# MAINSSMB_V1_4.net
KiCad netlist of a schematic drawn in Altium Designer
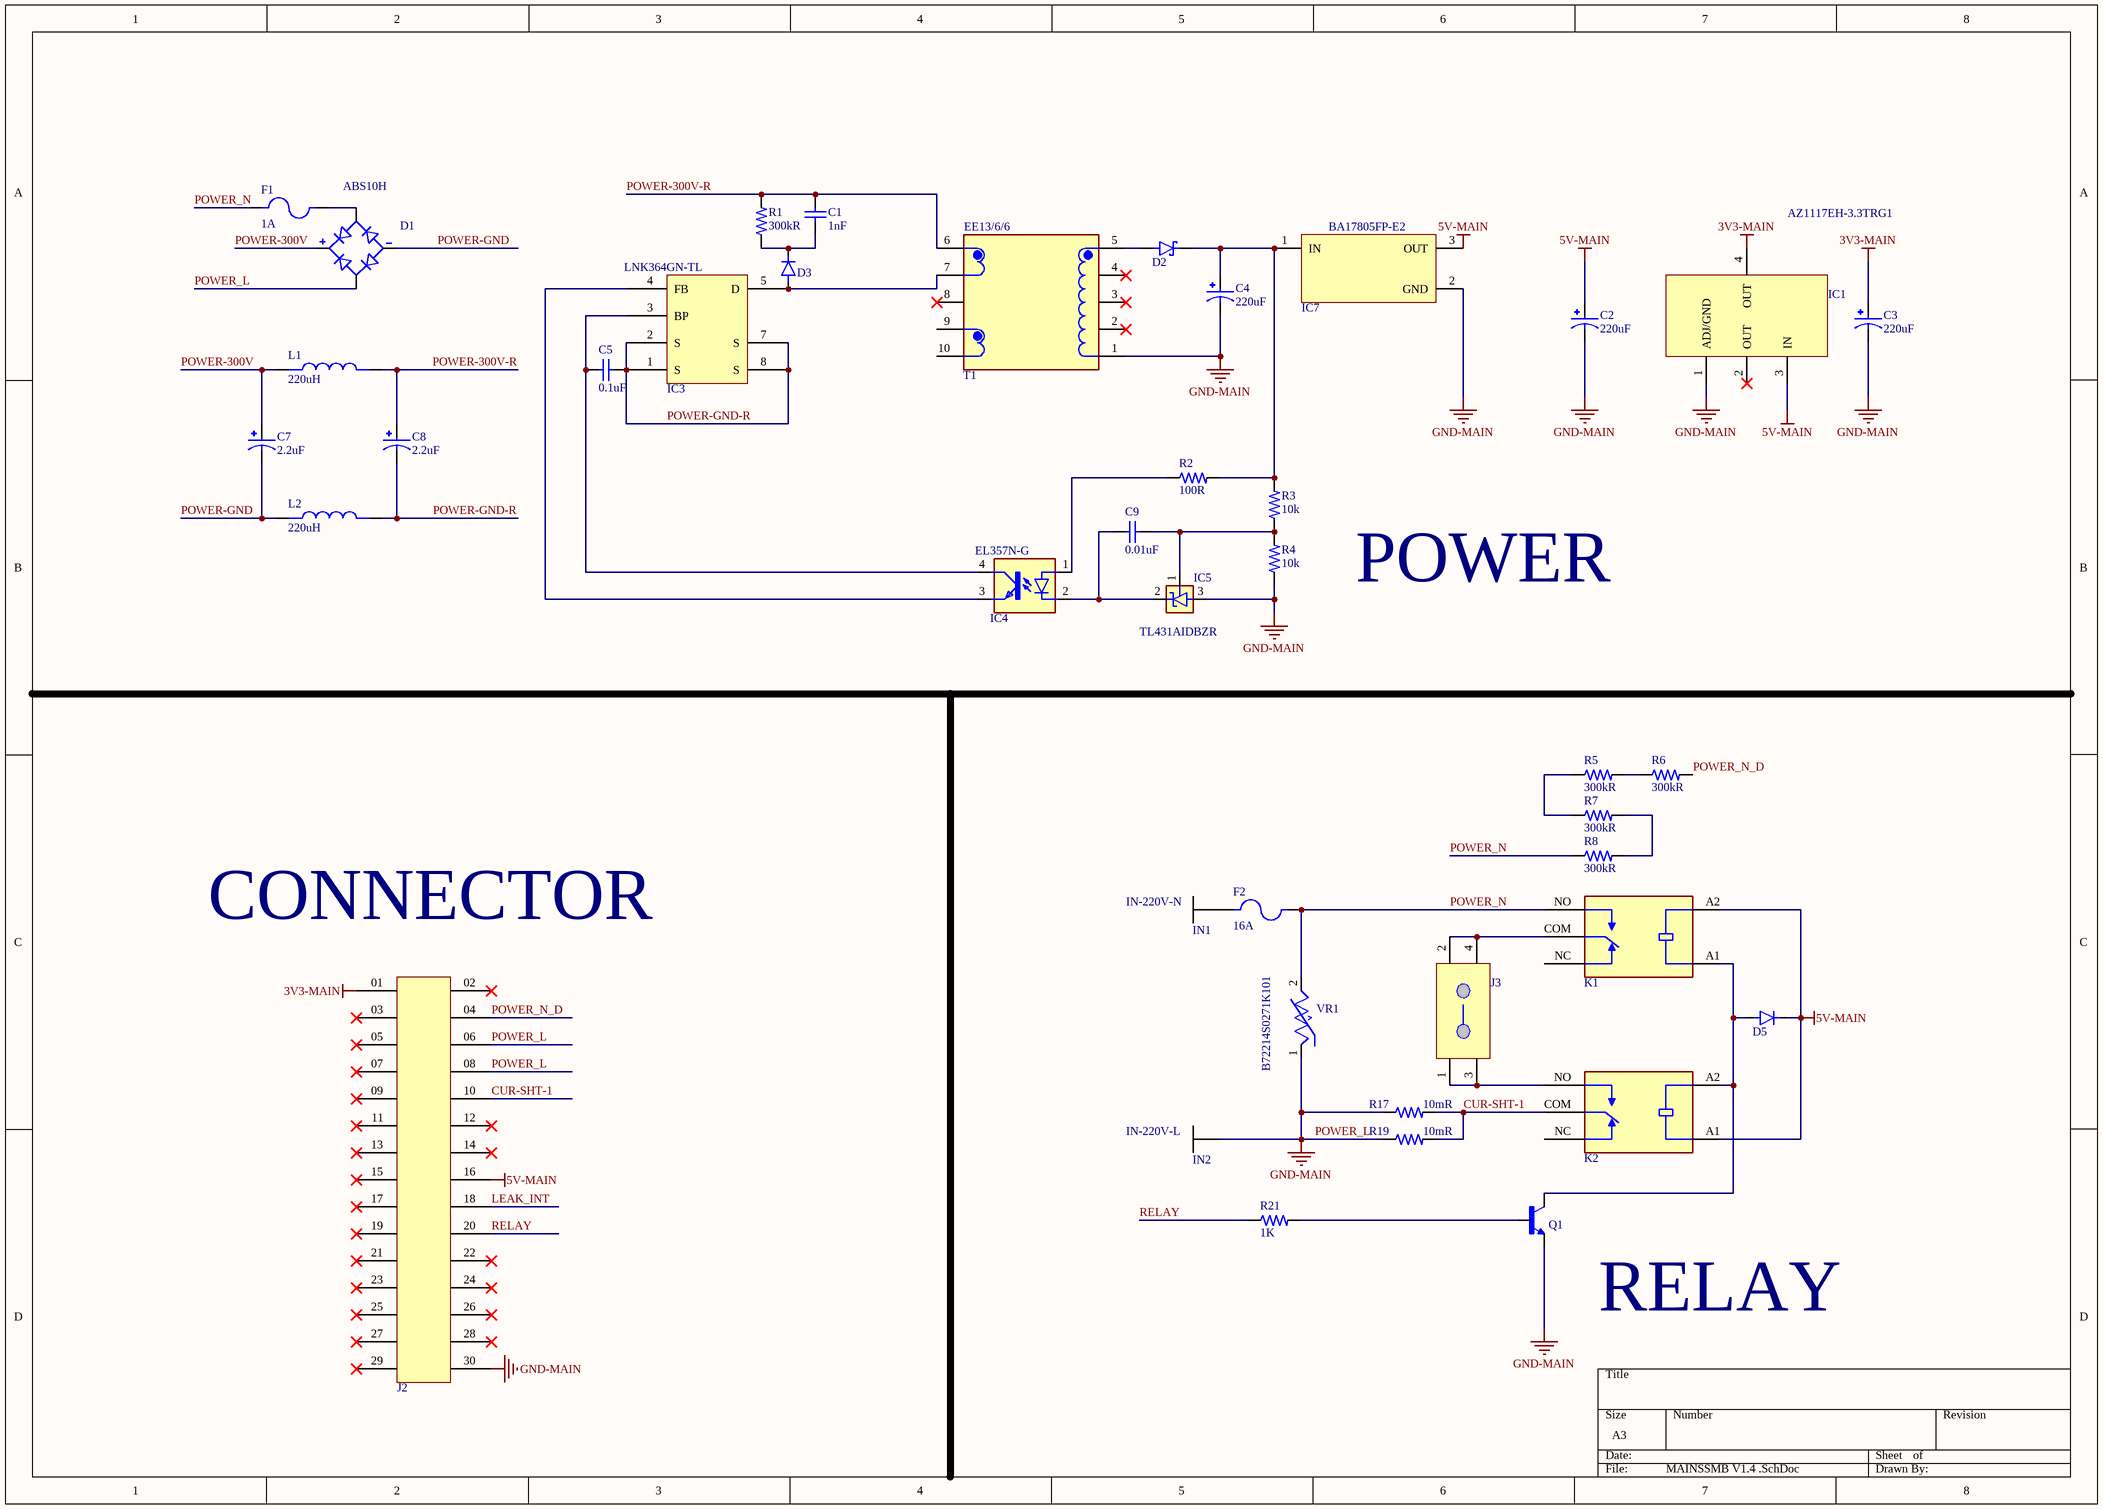
[diagram p0: MAINSSMB V1.4 .SchDoc]

(export (version "E")
  (design (tool "Eeschema 10.0.6"))
  (components
    (comp (ref "C1")
      (value "1nF")
      (footprint "TH-CAP-HxLxW-5.5x4.0x2.5-TDKC")
      (description "Capacitor Ceramic 0.001uF 50V C0G 5% 5mm T/R")
      (fields
        (field (name "MANUFACTURER") "TDK")
        (field (name "MANUFACTURER PART NUMBER") "FA28NP01H102JNU06")
        (field (name "DESIGNER") "TVBac")
      )
      (libsource (lib "Capacitors") (part "CAP; TH; 0.001uF; 50V; FA28NP01H102JNU06"))
    )
    (comp (ref "C2")
      (value "220uF")
      (footprint "SMD-DxLxW-6.3x6.6x6.6-PEC")
      (description "Cap Aluminum Polymer 220uF 16VDC 20% (6.3 X 5.9mm) SMD 0.022 Ohm 1040mA 1000h 125C T/R")
      (fields
        (field (name "MANUFACTURER") "Panasonic")
        (field (name "MANUFACTURER PART NUMBER") "16SVPK220M")
        (field (name "DESIGNER") "TVBac")
      )
      (libsource (lib "Capacitors") (part "CAP; 220uF; 16V; SMD; 16SVPK220M"))
    )
    (comp (ref "C3")
      (value "220uF")
      (footprint "SMD-DxLxW-6.3x6.6x6.6-PEC")
      (description "Cap Aluminum Polymer 220uF 10VDC 20%( 6.3 X 5.9mm) SMD 0.02 Ohm 2700mA 2000h 105C T/R")
      (fields
        (field (name "MANUFACTURER") "Panasonic")
        (field (name "MANUFACTURER PART NUMBER") "10SVPE220M")
        (field (name "DESIGNER") "TVBac")
      )
      (libsource (lib "Capacitors") (part "CAP; 220uF; 10V; SMD; 10SVPE220M"))
    )
    (comp (ref "C4")
      (value "220uF")
      (footprint "SMD-DxLxW-6.3x6.6x6.6-PEC")
      (description "Cap Aluminum Polymer 220uF 16VDC 20% (6.3 X 5.9mm) SMD 0.022 Ohm 1040mA 1000h 125C T/R")
      (fields
        (field (name "MANUFACTURER") "Panasonic")
        (field (name "MANUFACTURER PART NUMBER") "16SVPK220M")
        (field (name "DESIGNER") "TVBac")
      )
      (libsource (lib "Capacitors") (part "CAP; 220uF; 16V; SMD; 16SVPK220M"))
    )
    (comp (ref "C5")
      (value "0.1uF")
      (footprint "SMD-CAP-0603-YAGEO")
      (description "Multilayer Ceramic Capacitor, 0.1 uF, 50 V, ï¿½ 5%, X7R, 0603 [1608 Metric]")
      (fields
        (field (name "MANUFACTURER") "Yageo")
        (field (name "MANUFACTURER PART NUMBER") "CC0603JRX7R9BB104")
        (field (name "DESIGNER") "TVBac")
      )
      (libsource (lib "Capacitors") (part "CAP; 0.1uF; 50V; 0603; SMD; CC0603JRX7R9BB104"))
    )
    (comp (ref "C7")
      (value "2.2uF")
      (footprint "TH-CAP-HxD-12.5x8.0-PEC")
      (description "Cap Aluminum Lytic 2.2uF 400V 20% (8 X 11.5mm) Radial 3.5mm 50mA 2000h 85C Automotive Bulk")
      (fields
        (field (name "MANUFACTURER") "Panasonic")
        (field (name "MANUFACTURER PART NUMBER") "ECA-2GM2R2")
        (field (name "DESIGNER") "TVBac")
      )
      (libsource (lib "Capacitors") (part "CAP; TH; 2.2uF; 400V; ECA-2GM2R2"))
    )
    (comp (ref "C8")
      (value "2.2uF")
      (footprint "TH-CAP-HxD-12.5x8.0-PEC")
      (description "Cap Aluminum Lytic 2.2uF 400V 20% (8 X 11.5mm) Radial 3.5mm 50mA 2000h 85C Automotive Bulk")
      (fields
        (field (name "MANUFACTURER") "Panasonic")
        (field (name "MANUFACTURER PART NUMBER") "ECA-2GM2R2")
        (field (name "DESIGNER") "TVBac")
      )
      (libsource (lib "Capacitors") (part "CAP; TH; 2.2uF; 400V; ECA-2GM2R2"))
    )
    (comp (ref "C9")
      (value "0.01uF")
      (footprint "SMD-CAP-0603-YAGEO")
      (description "Surface Mount Ceramic Multilayer Capacitor 0.01uF 5% X7R 25V 0603 Paper T/R")
      (fields
        (field (name "MANUFACTURER") "Yageo")
        (field (name "MANUFACTURER PART NUMBER") "CC0603JRX7R8BB103")
        (field (name "DESIGNER") "TVBac")
      )
      (libsource (lib "Capacitors") (part "CAP; 0.01uF; 25V; 0603; SMD; CC0603JRX7R8BB103"))
    )
    (comp (ref "D1")
      (value "Bridge Rectifier Single Phase Standard 1 kV Surface Mount ABS")
      (footprint "DIODE-SMD-4-TSC")
      (description "Bridge Rectifiers 1A, 1000V, Standard Bridge Rectifier")
      (fields
        (field (name "MANUFACTURER") "Taiwan Semiconductor")
        (field (name "MANUFACTURER PART NUMBER") "ABS10H")
        (field (name "DESIGNER") "TVBac")
      )
      (libsource (lib "Diode") (part "DIODE; SMD; ABS10H"))
    )
    (comp (ref "D2")
      (value "Diode 40 V 3A Surface Mount DO-214AC (SMA)")
      (footprint "SMD-DO-214AC-214-CT")
      (description "Diode Schottky Si 40V 3A 2-Pin SMA T/R")
      (fields
        (field (name "MANUFACTURER") "Comchip")
        (field (name "MANUFACTURER PART NUMBER") "SS34-HF")
        (field (name "DESIGNER") "TVBac")
      )
      (libsource (lib "Smartsocket") (part "DIODE; SMD; SCHOTTKY; SS34-HF"))
    )
    (comp (ref "D3")
      (value "Diode 1000 V 1A Surface Mount SOD-123FL")
      (footprint "SOD-123FL-SMCDS")
      (description "Diode Gen Purp 1KV 1A SOD123FL")
      (fields
        (field (name "MANUFACTURER") "Sangdest Microelectronics")
        (field (name "MANUFACTURER PART NUMBER") "1N4007FL")
        (field (name "DESIGNER") "TVBac")
      )
      (libsource (lib "Diode") (part "DIODE; SMD; 1N4007FLN4007;"))
    )
    (comp (ref "D5")
      (value "Diode 1000 V 1A Surface Mount SOD-123FL")
      (footprint "SOD-123FL-SMCDS")
      (description "Diode Gen Purp 1KV 1A SOD123FL")
      (fields
        (field (name "MANUFACTURER") "Sangdest Microelectronics")
        (field (name "MANUFACTURER PART NUMBER") "1N4007FL")
        (field (name "DESIGNER") "TVBac")
      )
      (libsource (lib "Diode") (part "DIODE; SMD; 1N4007FLN4007;"))
    )
    (comp (ref "F1")
      (value "1A")
      (footprint "FUSE-HxLxW-8.0x8.5x4.0-LI")
      (description "Fuse Subminiature Slow Blow Acting 1A 300V Radial 8.5 X 4 X 8mm Ammo Pack")
      (fields
        (field (name "MANUFACTURER") "Littelfuse Wickmann")
        (field (name "MANUFACTURER PART NUMBER") "36911000000")
        (field (name "DESIGNER") "TVBac")
      )
      (libsource (lib "Smartsocket") (part "FUSE; 1A; 36911000000"))
    )
    (comp (ref "F2")
      (value "16A")
      (footprint "FUSE-3.6mmx10mm-AXIAL")
      (fields
        (field (name "MANUFACTURER") "Schurter")
        (field (name "MANUFACTURER PART NUMBER") "0031.8211")
        (field (name "Comment") "FUSE; 16A; 0031.8211_1")
        (field (name "DESIGNER") "TVBac")
      )
      (libsource (lib "Socket") (part "FUSE; 16A; 0031.8211_1"))
    )
    (comp (ref "IC1")
      (value "Linear Voltage Regulator IC Positive Fixed 1 Output 1A SOT-223-3")
      (footprint "IC:SOT-223-3-DI")
      (description "Linear Voltage Regulator IC 1 Output 1A SOT-223")
      (fields
        (field (name "MF") "Diodes Inc.")
        (field (name "MP") "AZ1117EH-3.3TRG1")
        (field (name "DESIGNER") "TVBac")
      )
      (libsource (lib "IC") (part "LDO; 3V3; 1A; SMD; AZ1117EH-3.3TRG1"))
    )
    (comp (ref "IC3")
      (value "Converter Offline Flyback Topology 132kHz SMD-8B")
      (footprint "SMD-8B-PI")
      (description "AC to DC Switching Converter Off-Line Switcher 140kHz 7-Pin SMD-B / IC OFFLINE SWIT HV 8SMD")
      (fields
        (field (name "MANUFACTURER") "Power Integrations")
        (field (name "MANUFACTURER PART NUMBER") "LNK364GN-TL")
        (field (name "DESIGNER") "TVBac")
      )
      (libsource (lib "Smartsocket") (part "LNK364GN-TL"))
    )
    (comp (ref "IC4")
      (value "Optoisolator Transistor Output 3750Vrms 1 Channel 4-SOP (2.54mm)")
      (footprint "SOP-4")
      (description "Transistor Output Optocoupler, 1-Element, 3750V Isolation")
      (fields (field (name "MANUFACTURER") "Everlight") (field (name "MANUFACTURER PART NUMBER") "EL357N-G"))
      (libsource (lib "IC") (part "ISO; 1CH; EL357N-G"))
    )
    (comp (ref "IC5")
      (value "Shunt Voltage Reference IC Adjustable 2.495V 36 VV ±1% 100 mA SOT-23-3")
      (footprint "SOT-23-3-DS")
      (description "V-Ref Adjustable 2.495V to 36V 100mA Automotive 3-Pin SOT-23 T/R")
      (fields
        (field (name "MANUFACTURER") "Texas Instruments")
        (field (name "MANUFACTURER PART NUMBER") "TL431AIDBZR")
        (field (name "TOLERANCE") "1%")
        (field (name "DESIGNER") "TVBac")
      )
      (libsource (lib "IC") (part "TL431AIDBZR; MIRROID;"))
    )
    (comp (ref "IC7")
      (value "Linear Voltage Regulator IC Positive Fixed 1 Output 1A TO-252")
      (footprint "TO252-3-RS")
      (description "Linear Voltage Regulator, Fixed, Positive Output, 7.5 V to 25 V, 5V, 1A, 3 Pins, TO-252 (DPAK)")
      (fields
        (field (name "MANUFACTURER") "Rohm")
        (field (name "MANUFACTURER PART NUMBER") "BA17805FP-E2")
        (field (name "DESIGNER") "TVBac")
      )
      (libsource (lib "IC") (part "LDO; 5V; 1A; BA17805FP-E2"))
    )
    (comp (ref "IN1")
      (value "INPUT")
      (footprint "INPUT-2.0x3.5")
      (fields (field (name "DESIGNER") "TVBac"))
      (libsource (lib "Socket") (part "INPUT-2.0x3.5"))
    )
    (comp (ref "IN2")
      (value "INPUT")
      (footprint "INPUT-2.0x3.5")
      (fields (field (name "DESIGNER") "TVBac"))
      (libsource (lib "Socket") (part "INPUT-2.0x3.5"))
    )
    (comp (ref "J2")
      (value "30 Position Elevated Socket Connector 0.100\" (2.54mm) Through Hole Gold")
      (footprint "HEADER-2.54-15x2-N3D")
      (description "Connector Receptacle 30 Position 0.100\" (2.54mm) Gold Through Hole")
      (fields
        (field (name "MANUFACTURER") "Samtec")
        (field (name "MANUFACTURER PART NUMBER") "ESQ-115-12-G-D")
        (field (name "DESIGNER") "TVBac")
      )
      (libsource (lib "Socket") (part "HEADER; 15x2PIN; 2.54; VER; ESQ-115-12-G-D; N3D"))
    )
    (comp (ref "J3")
      (value "Connector Header Through Hole 4 position 0.100\" (2.54mm)")
      (footprint "SOCKET-SINGLE-WEV1081H")
      (description "Conn Unshrouded Header HDR 4 POS 2.54mm Solder ST Thru-Hole Automotive Bulk")
      (fields
        (field (name "MANUFACTURER") "Samtec")
        (field (name "MANUFACTURER PART NUMBER") "TSW-104-14-L-S")
        (field (name "DESIGNER") "TVBac")
      )
      (libsource (lib "Socket") (part "SOCKET; SINGLE;"))
    )
    (comp (ref "K1")
      (value "JQ1P-5V-F")
      (footprint "RELAY-JQ1P-10A-HxLxW-15.6x20.5x10.0-PEW")
      (description "RELAY GEN PURPOSE SPDT 10A 5V")
      (fields (field (name "DESIGNER") "TVBac"))
      (libsource (lib "Relay") (part "RELAY; SINGLE; 5VDC; CMP-05607-000163-1"))
    )
    (comp (ref "K2")
      (value "JQ1P-5V-F")
      (footprint "RELAY-JQ1P-10A-HxLxW-15.6x20.5x10.0-PEW")
      (description "RELAY GEN PURPOSE SPDT 10A 5V")
      (fields (field (name "DESIGNER") "TVBac"))
      (libsource (lib "Relay") (part "RELAY; SINGLE; 5VDC; CMP-05607-000163-1"))
    )
    (comp (ref "L1")
      (value "220uH")
      (footprint "SMD-HxLxW-1.8x4.0x4.0-ALLC")
      (description "Power Inductor (SMD), 220 uH, ± 20%, 250 mA, Shielded, 330 mA, 4mm x 4mm x 1.8mm")
      (fields
        (field (name "MANUFACTURER") "Abracon")
        (field (name "MANUFACTURER PART NUMBER") "ASPI-0418FS-221M-T3")
        (field (name "DESIGNER") "TVBac")
      )
      (libsource (lib "Inductors") (part "IND; 220uH; 250mA; ASPI-0418FS-221M-T3"))
    )
    (comp (ref "L2")
      (value "220uH")
      (footprint "SMD-HxLxW-1.8x4.0x4.0-ALLC")
      (description "Power Inductor (SMD), 220 uH, ± 20%, 250 mA, Shielded, 330 mA, 4mm x 4mm x 1.8mm")
      (fields
        (field (name "MANUFACTURER") "Abracon")
        (field (name "MANUFACTURER PART NUMBER") "ASPI-0418FS-221M-T3")
        (field (name "DESIGNER") "TVBac")
      )
      (libsource (lib "Inductors") (part "IND; 220uH; 250mA; ASPI-0418FS-221M-T3"))
    )
    (comp (ref "Q1")
      (value "Bipolar (BJT) Transistor NPN 45 V 500 mA 100MHz 300 mW Surface Mount SOT-23-3 (TO-236)")
      (footprint "SOT-23-3-ONSEMI")
      (description "Single Bipolar Transistor, NPN, 45 V, 500 mA, 225 mW, SOT-23 (TO-236), 3 Pins, Surface Mount")
      (fields
        (field (name "MANUFACTURER") "ON Semiconductor")
        (field (name "MANUFACTURER PART NUMBER") "BC817-25LT1G")
        (field (name "DESIGNER") "TVBac")
      )
      (libsource (lib "Transistors") (part "TRAN; NPN; 500mA;V;  BC817-25LT1G"))
    )
    (comp (ref "R1")
      (value "300kR")
      (footprint "SMD-RES-1206-RS")
      (description "Res Thick Film 1206 300K Ohm 1% 0.5W(1/2W) ±100ppm/C Epoxy Resin Pad SMD Automotive T/R")
      (fields
        (field (name "MANUFACTURER") "Rohm")
        (field (name "MANUFACTURER PART NUMBER") "ESR18EZPF3003")
        (field (name "DESIGNER") "TVBac")
      )
      (libsource (lib "Resistors") (part "RES; 300K; 1206; ESR18EZPF3003"))
    )
    (comp (ref "R2")
      (value "100R")
      (footprint "SMD-RES-0603-RS")
      (description "Res Thick Film 0603 100 Ohm 1% 0.1W(1/10W) ±100ppm/C Pad SMD T/R Automotive AEC-Q200")
      (fields
        (field (name "MANUFACTURER") "Rohm")
        (field (name "MANUFACTURER PART NUMBER") "KTR03EZPF1000")
        (field (name "DESIGNER") "TVBac")
      )
      (libsource (lib "Resistors") (part "RES; 100R; 0603; SMD; KTR03EZPF1000"))
    )
    (comp (ref "R3")
      (value "10k")
      (footprint "SMD-RES-0603-SEI")
      (description "SMD Chip Resistor, 10 kOhm, ± 1%, 250 mW, 0603 [1608 Metric], Thick Film, Anti-Surge")
      (fields
        (field (name "MANUFACTURER") "Rohm")
        (field (name "MANUFACTURER PART NUMBER") "ESR03EZPF1002")
        (field (name "DESIGNER") "TVBac")
      )
      (libsource (lib "Resistors") (part "RES; 10K; 0603; SMD; ESR03EZPF1002"))
    )
    (comp (ref "R4")
      (value "10k")
      (footprint "SMD-RES-0603-SEI")
      (description "SMD Chip Resistor, 10 kOhm, ± 1%, 250 mW, 0603 [1608 Metric], Thick Film, Anti-Surge")
      (fields
        (field (name "MANUFACTURER") "Rohm")
        (field (name "MANUFACTURER PART NUMBER") "ESR03EZPF1002")
        (field (name "DESIGNER") "TVBac")
      )
      (libsource (lib "Resistors") (part "RES; 10K; 0603; SMD; ESR03EZPF1002"))
    )
    (comp (ref "R5")
      (value "300kR")
      (footprint "SMD-RES-0603-RS")
      (description "Res High Voltage Thick Film 0603 300k Ohm 1% 1/10W ±100ppm/°C Molded Paper T/R")
      (fields
        (field (name "MANUFACTURER") "Rohm")
        (field (name "MANUFACTURER PART NUMBER") "KTR03EZPF3003")
        (field (name "DESIGNER") "TVBac")
      )
      (libsource (lib "Resistors") (part "RES; 300K; 0603; SMD; KTR03EZPF3003"))
    )
    (comp (ref "R6")
      (value "300kR")
      (footprint "SMD-RES-0603-RS")
      (description "Res High Voltage Thick Film 0603 300k Ohm 1% 1/10W ±100ppm/°C Molded Paper T/R")
      (fields
        (field (name "MANUFACTURER") "Rohm")
        (field (name "MANUFACTURER PART NUMBER") "KTR03EZPF3003")
        (field (name "DESIGNER") "TVBac")
      )
      (libsource (lib "Resistors") (part "RES; 300K; 0603; SMD; KTR03EZPF3003"))
    )
    (comp (ref "R7")
      (value "300kR")
      (footprint "SMD-RES-0603-RS")
      (description "Res High Voltage Thick Film 0603 300k Ohm 1% 1/10W ±100ppm/°C Molded Paper T/R")
      (fields
        (field (name "MANUFACTURER") "Rohm")
        (field (name "MANUFACTURER PART NUMBER") "KTR03EZPF3003")
        (field (name "DESIGNER") "TVBac")
      )
      (libsource (lib "Resistors") (part "RES; 300K; 0603; SMD; KTR03EZPF3003"))
    )
    (comp (ref "R8")
      (value "300kR")
      (footprint "SMD-RES-0603-RS")
      (description "Res High Voltage Thick Film 0603 300k Ohm 1% 1/10W ±100ppm/°C Molded Paper T/R")
      (fields
        (field (name "MANUFACTURER") "Rohm")
        (field (name "MANUFACTURER PART NUMBER") "KTR03EZPF3003")
        (field (name "DESIGNER") "TVBac")
      )
      (libsource (lib "Resistors") (part "RES; 300K; 0603; SMD; KTR03EZPF3003"))
    )
    (comp (ref "R17")
      (value "10mR")
      (footprint "SMD-RES-2512-VD")
      (description "Res Current Sense Metal Plate 2512 0.01 Ohm 1% 3W ±110ppm/°C Molded T/R")
      (fields
        (field (name "MANUFACTURER") "Vishay")
        (field (name "MANUFACTURER PART NUMBER") "WFMA2512R0100FEA")
        (field (name "DESIGNER") "TVBac")
      )
      (libsource (lib "Smartsocket") (part "RES; SHUNT; 10mOhm; SMD; WFMA2512R0100FEA"))
    )
    (comp (ref "R19")
      (value "10mR")
      (footprint "SMD-RES-2512-VD")
      (description "Res Current Sense Metal Plate 2512 0.01 Ohm 1% 3W ±110ppm/°C Molded T/R")
      (fields
        (field (name "MANUFACTURER") "Vishay")
        (field (name "MANUFACTURER PART NUMBER") "WFMA2512R0100FEA")
        (field (name "DESIGNER") "TVBac")
      )
      (libsource (lib "Smartsocket") (part "RES; SHUNT; 10mOhm; SMD; WFMA2512R0100FEA"))
    )
    (comp (ref "R21")
      (value "1K")
      (footprint "SMD-RES-0603-SEI")
      (description "SMD Chip Resistor, 1 kOhm, ± 1%, 250 mW, 0603 [1608 Metric], Thick Film, Anti-Surge")
      (fields
        (field (name "MANUFACTURER") "Rohm")
        (field (name "MANUFACTURER PART NUMBER") "ESR03EZPF1001")
        (field (name "DESIGNER") "TVBac")
      )
      (libsource (lib "Smartsocket") (part "RES; 1K; 0603; SMD; ESR03EZPF1001"))
    )
    (comp (ref "T1")
      (value "For SMPS Transformer 500VAC Isolation Through Hole")
      (footprint "EE13 - POWER")
      (description "OFFLINE TRANSFORMER 6W EE13/7/6")
      (fields (field (name "MF") "Wurth Electronics Inc") (field (name "MP") "EE13/6/6"))
      (libsource (lib "Transformer") (part "EE13/6/6-Power"))
    )
    (comp (ref "VR1")
      (value "VAR; B72214S0271K101")
      (footprint "VARISTOR-TDK")
      (description "Var MOV 275VAC/350VDC 4500A 430V Thru-Hole Radial Automotive Bulk")
      (fields
        (field (name "MANUFACTURER") "TDK EPCOS")
        (field (name "MANUFACTURER PART NUMBER") "B72214S0271K101")
      )
      (libsource (lib "Capacitors") (part "VAR; B72214S0271K101"))
    )
  )
  (nets
    (net (code "1") (name "/CUR-SHT-1") (class "Default")
      (node (ref "J2") (pin "10") (pinfunction "10_10") (pintype "passive"))
      (node (ref "K2") (pin "COM") (pinfunction "COM_COM") (pintype "passive"))
      (node (ref "R17") (pin "2") (pinfunction "2_2") (pintype "passive"))
      (node (ref "R19") (pin "2") (pinfunction "2_2") (pintype "passive"))
    )
    (net (code "2") (name "/LEAK_INT") (class "Default")
      (node (ref "J2") (pin "18") (pinfunction "18_18") (pintype "passive"))
    )
    (net (code "3") (name "/POWER-300V") (class "Default")
      (node (ref "C7") (pin "1") (pinfunction "1_1") (pintype "passive"))
      (node (ref "D1") (pin "POS") (pinfunction "POS_POS") (pintype "passive"))
      (node (ref "L1") (pin "1") (pinfunction "1_1") (pintype "passive"))
    )
    (net (code "4") (name "/POWER-300V-R") (class "Default")
      (node (ref "C1") (pin "2") (pinfunction "2_2") (pintype "passive"))
      (node (ref "C8") (pin "1") (pinfunction "1_1") (pintype "passive"))
      (node (ref "L1") (pin "2") (pinfunction "2_2") (pintype "passive"))
      (node (ref "R1") (pin "2") (pinfunction "2_2") (pintype "passive"))
      (node (ref "T1") (pin "6") (pinfunction "6_6") (pintype "passive"))
    )
    (net (code "5") (name "/POWER-GND") (class "Default")
      (node (ref "C7") (pin "2") (pinfunction "2_2") (pintype "passive"))
      (node (ref "D1") (pin "NEG") (pinfunction "NEG_NEG") (pintype "passive"))
      (node (ref "L2") (pin "1") (pinfunction "1_1") (pintype "passive"))
    )
    (net (code "6") (name "/POWER-GND-R") (class "Default")
      (node (ref "C5") (pin "2") (pinfunction "2_2") (pintype "passive"))
      (node (ref "C8") (pin "2") (pinfunction "2_2") (pintype "passive"))
      (node (ref "IC3") (pin "1") (pinfunction "S_1") (pintype "passive"))
      (node (ref "IC3") (pin "2") (pinfunction "S_2") (pintype "passive"))
      (node (ref "IC3") (pin "7") (pinfunction "S_7") (pintype "passive"))
      (node (ref "IC3") (pin "8") (pinfunction "S_8") (pintype "passive"))
      (node (ref "L2") (pin "2") (pinfunction "2_2") (pintype "passive"))
    )
    (net (code "7") (name "/POWER_N") (class "Default")
      (node (ref "F1") (pin "1") (pinfunction "1_1") (pintype "passive"))
      (node (ref "F2") (pin "2") (pinfunction "2_2") (pintype "passive"))
      (node (ref "K1") (pin "NO") (pinfunction "NO_NO") (pintype "passive"))
      (node (ref "R8") (pin "1") (pinfunction "1_1") (pintype "passive"))
      (node (ref "VR1") (pin "2") (pinfunction "2_2") (pintype "passive"))
    )
    (net (code "8") (name "/POWER_N_D") (class "Default")
      (node (ref "J2") (pin "04") (pinfunction "04_04") (pintype "passive"))
      (node (ref "R6") (pin "2") (pinfunction "2_2") (pintype "passive"))
    )
    (net (code "9") (name "/RELAY") (class "Default")
      (node (ref "J2") (pin "20") (pinfunction "20_20") (pintype "passive"))
      (node (ref "R21") (pin "1") (pinfunction "1_1") (pintype "passive"))
    )
    (net (code "10") (name "3V3-MAIN") (class "Default")
      (node (ref "C3") (pin "1") (pinfunction "1_1") (pintype "passive"))
      (node (ref "IC1") (pin "4") (pinfunction "OUT_4") (pintype "passive"))
      (node (ref "J2") (pin "01") (pinfunction "01_01") (pintype "passive"))
    )
    (net (code "11") (name "5V-MAIN") (class "Default")
      (node (ref "C2") (pin "1") (pinfunction "1_1") (pintype "passive"))
      (node (ref "D5") (pin "K") (pinfunction "K_K") (pintype "passive"))
      (node (ref "IC1") (pin "3") (pinfunction "IN_3") (pintype "passive"))
      (node (ref "IC7") (pin "3") (pinfunction "OUT_3") (pintype "passive"))
      (node (ref "J2") (pin "16") (pinfunction "16_16") (pintype "passive"))
      (node (ref "K1") (pin "A2") (pinfunction "A2_A2") (pintype "passive"))
      (node (ref "K2") (pin "A1") (pinfunction "A1_A1") (pintype "passive"))
    )
    (net (code "12") (name "GND-MAIN") (class "Default")
      (node (ref "C2") (pin "2") (pinfunction "2_2") (pintype "passive"))
      (node (ref "C3") (pin "2") (pinfunction "2_2") (pintype "passive"))
      (node (ref "C4") (pin "2") (pinfunction "2_2") (pintype "passive"))
      (node (ref "D1") (pin "AC2") (pinfunction "AC2_AC2") (pintype "passive"))
      (node (ref "IC1") (pin "1") (pinfunction "ADJ/GND_1") (pintype "passive"))
      (node (ref "IC5") (pin "3") (pinfunction "ANODE_3") (pintype "passive"))
      (node (ref "IC7") (pin "2") (pinfunction "GND_2") (pintype "passive"))
      (node (ref "IN2") (pin "1") (pinfunction "IN_1") (pintype "passive"))
      (node (ref "J2") (pin "06") (pinfunction "06_06") (pintype "passive"))
      (node (ref "J2") (pin "08") (pinfunction "08_08") (pintype "passive"))
      (node (ref "J2") (pin "30") (pinfunction "30_30") (pintype "passive"))
      (node (ref "Q1") (pin "2") (pinfunction "E_2") (pintype "passive"))
      (node (ref "R17") (pin "1") (pinfunction "1_1") (pintype "passive"))
      (node (ref "R19") (pin "1") (pinfunction "1_1") (pintype "passive"))
      (node (ref "R4") (pin "1") (pinfunction "1_1") (pintype "passive"))
      (node (ref "T1") (pin "1") (pinfunction "1_1") (pintype "passive"))
      (node (ref "VR1") (pin "1") (pinfunction "1_1") (pintype "passive"))
    )
    (net (code "13") (name "Net-(C1-Pad1)") (class "Default")
      (node (ref "C1") (pin "1") (pinfunction "1_1") (pintype "passive"))
      (node (ref "D3") (pin "K") (pinfunction "K_K") (pintype "passive"))
      (node (ref "R1") (pin "1") (pinfunction "1_1") (pintype "passive"))
    )
    (net (code "14") (name "Net-(D1-PadAC1)") (class "Default")
      (node (ref "D1") (pin "AC1") (pinfunction "AC1_AC1") (pintype "passive"))
      (node (ref "F1") (pin "2") (pinfunction "2_2") (pintype "passive"))
    )
    (net (code "15") (name "Net-(D2-A)") (class "Default")
      (node (ref "D2") (pin "2") (pinfunction "A_2") (pintype "passive"))
      (node (ref "T1") (pin "5") (pinfunction "5_5") (pintype "passive"))
    )
    (net (code "16") (name "Net-(D2-K)") (class "Default")
      (node (ref "C4") (pin "1") (pinfunction "1_1") (pintype "passive"))
      (node (ref "D2") (pin "1") (pinfunction "K_1") (pintype "passive"))
      (node (ref "IC7") (pin "1") (pinfunction "IN_1") (pintype "passive"))
      (node (ref "R2") (pin "2") (pinfunction "2_2") (pintype "passive"))
      (node (ref "R3") (pin "2") (pinfunction "2_2") (pintype "passive"))
    )
    (net (code "17") (name "Net-(IC3-BP)") (class "Default")
      (node (ref "C5") (pin "1") (pinfunction "1_1") (pintype "passive"))
      (node (ref "IC3") (pin "3") (pinfunction "BP_3") (pintype "passive"))
      (node (ref "IC4") (pin "4") (pinfunction "COL_4") (pintype "passive"))
    )
    (net (code "18") (name "Net-(IC3-D)") (class "Default")
      (node (ref "D3") (pin "A") (pinfunction "A_A") (pintype "passive"))
      (node (ref "IC3") (pin "5") (pinfunction "D_5") (pintype "passive"))
      (node (ref "T1") (pin "7") (pinfunction "7_7") (pintype "passive"))
    )
    (net (code "19") (name "Net-(IC3-FB)") (class "Default")
      (node (ref "IC3") (pin "4") (pinfunction "FB_4") (pintype "passive"))
      (node (ref "IC4") (pin "3") (pinfunction "EMIT_3") (pintype "passive"))
    )
    (net (code "20") (name "Net-(IC4-A)") (class "Default")
      (node (ref "IC4") (pin "1") (pinfunction "A_1") (pintype "passive"))
      (node (ref "R2") (pin "1") (pinfunction "1_1") (pintype "passive"))
    )
    (net (code "21") (name "Net-(IC4-C)") (class "Default")
      (node (ref "C9") (pin "1") (pinfunction "1_1") (pintype "passive"))
      (node (ref "IC4") (pin "2") (pinfunction "C_2") (pintype "passive"))
      (node (ref "IC5") (pin "2") (pinfunction "CATHODE_2") (pintype "passive"))
    )
    (net (code "22") (name "Net-(IC5-REF)") (class "Default")
      (node (ref "C9") (pin "2") (pinfunction "2_2") (pintype "passive"))
      (node (ref "IC5") (pin "1") (pinfunction "REF_1") (pintype "passive"))
      (node (ref "R3") (pin "1") (pinfunction "1_1") (pintype "passive"))
      (node (ref "R4") (pin "2") (pinfunction "2_2") (pintype "passive"))
    )
    (net (code "23") (name "Net-(IN1-IN)") (class "Default")
      (node (ref "F2") (pin "1") (pinfunction "1_1") (pintype "passive"))
      (node (ref "IN1") (pin "1") (pinfunction "IN_1") (pintype "passive"))
    )
    (net (code "24") (name "Net-(J3-Pad1)") (class "Default")
      (node (ref "J3") (pin "1") (pinfunction "1_1") (pintype "passive"))
      (node (ref "J3") (pin "3") (pinfunction "3_3") (pintype "passive"))
      (node (ref "K2") (pin "NO") (pinfunction "NO_NO") (pintype "passive"))
    )
    (net (code "25") (name "Net-(J3-Pad2)") (class "Default")
      (node (ref "J3") (pin "2") (pinfunction "2_2") (pintype "passive"))
      (node (ref "J3") (pin "4") (pinfunction "4_4") (pintype "passive"))
      (node (ref "K1") (pin "COM") (pinfunction "COM_COM") (pintype "passive"))
    )
    (net (code "26") (name "Net-(Q1-B)") (class "Default")
      (node (ref "Q1") (pin "1") (pinfunction "B_1") (pintype "passive"))
      (node (ref "R21") (pin "2") (pinfunction "2_2") (pintype "passive"))
    )
    (net (code "27") (name "Net-(Q1-C)") (class "Default")
      (node (ref "D5") (pin "A") (pinfunction "A_A") (pintype "passive"))
      (node (ref "K1") (pin "A1") (pinfunction "A1_A1") (pintype "passive"))
      (node (ref "K2") (pin "A2") (pinfunction "A2_A2") (pintype "passive"))
      (node (ref "Q1") (pin "3") (pinfunction "C_3") (pintype "passive"))
    )
    (net (code "28") (name "Net-(R5-Pad1)") (class "Default")
      (node (ref "R5") (pin "1") (pinfunction "1_1") (pintype "passive"))
      (node (ref "R7") (pin "1") (pinfunction "1_1") (pintype "passive"))
    )
    (net (code "29") (name "Net-(R5-Pad2)") (class "Default")
      (node (ref "R5") (pin "2") (pinfunction "2_2") (pintype "passive"))
      (node (ref "R6") (pin "1") (pinfunction "1_1") (pintype "passive"))
    )
    (net (code "30") (name "Net-(R7-Pad2)") (class "Default")
      (node (ref "R7") (pin "2") (pinfunction "2_2") (pintype "passive"))
      (node (ref "R8") (pin "2") (pinfunction "2_2") (pintype "passive"))
    )
    (net (code "31") (name "unconnected-(IC1-OUT-Pad2)") (class "Default")
      (node (ref "IC1") (pin "2") (pinfunction "OUT_2") (pintype "passive+no_connect"))
    )
    (net (code "32") (name "unconnected-(J2-Pad02)") (class "Default")
      (node (ref "J2") (pin "02") (pinfunction "02_02") (pintype "passive+no_connect"))
    )
    (net (code "33") (name "unconnected-(J2-Pad03)") (class "Default")
      (node (ref "J2") (pin "03") (pinfunction "03_03") (pintype "passive+no_connect"))
    )
    (net (code "34") (name "unconnected-(J2-Pad05)") (class "Default")
      (node (ref "J2") (pin "05") (pinfunction "05_05") (pintype "passive+no_connect"))
    )
    (net (code "35") (name "unconnected-(J2-Pad07)") (class "Default")
      (node (ref "J2") (pin "07") (pinfunction "07_07") (pintype "passive+no_connect"))
    )
    (net (code "36") (name "unconnected-(J2-Pad09)") (class "Default")
      (node (ref "J2") (pin "09") (pinfunction "09_09") (pintype "passive+no_connect"))
    )
    (net (code "37") (name "unconnected-(J2-Pad11)") (class "Default")
      (node (ref "J2") (pin "11") (pinfunction "11_11") (pintype "passive+no_connect"))
    )
    (net (code "38") (name "unconnected-(J2-Pad12)") (class "Default")
      (node (ref "J2") (pin "12") (pinfunction "12_12") (pintype "passive+no_connect"))
    )
    (net (code "39") (name "unconnected-(J2-Pad13)") (class "Default")
      (node (ref "J2") (pin "13") (pinfunction "13_13") (pintype "passive+no_connect"))
    )
    (net (code "40") (name "unconnected-(J2-Pad14)") (class "Default")
      (node (ref "J2") (pin "14") (pinfunction "14_14") (pintype "passive+no_connect"))
    )
    (net (code "41") (name "unconnected-(J2-Pad15)") (class "Default")
      (node (ref "J2") (pin "15") (pinfunction "15_15") (pintype "passive+no_connect"))
    )
    (net (code "42") (name "unconnected-(J2-Pad17)") (class "Default")
      (node (ref "J2") (pin "17") (pinfunction "17_17") (pintype "passive+no_connect"))
    )
    (net (code "43") (name "unconnected-(J2-Pad19)") (class "Default")
      (node (ref "J2") (pin "19") (pinfunction "19_19") (pintype "passive+no_connect"))
    )
    (net (code "44") (name "unconnected-(J2-Pad21)") (class "Default")
      (node (ref "J2") (pin "21") (pinfunction "21_21") (pintype "passive+no_connect"))
    )
    (net (code "45") (name "unconnected-(J2-Pad22)") (class "Default")
      (node (ref "J2") (pin "22") (pinfunction "22_22") (pintype "passive+no_connect"))
    )
    (net (code "46") (name "unconnected-(J2-Pad23)") (class "Default")
      (node (ref "J2") (pin "23") (pinfunction "23_23") (pintype "passive+no_connect"))
    )
    (net (code "47") (name "unconnected-(J2-Pad24)") (class "Default")
      (node (ref "J2") (pin "24") (pinfunction "24_24") (pintype "passive+no_connect"))
    )
    (net (code "48") (name "unconnected-(J2-Pad25)") (class "Default")
      (node (ref "J2") (pin "25") (pinfunction "25_25") (pintype "passive+no_connect"))
    )
    (net (code "49") (name "unconnected-(J2-Pad26)") (class "Default")
      (node (ref "J2") (pin "26") (pinfunction "26_26") (pintype "passive+no_connect"))
    )
    (net (code "50") (name "unconnected-(J2-Pad27)") (class "Default")
      (node (ref "J2") (pin "27") (pinfunction "27_27") (pintype "passive+no_connect"))
    )
    (net (code "51") (name "unconnected-(J2-Pad28)") (class "Default")
      (node (ref "J2") (pin "28") (pinfunction "28_28") (pintype "passive+no_connect"))
    )
    (net (code "52") (name "unconnected-(J2-Pad29)") (class "Default")
      (node (ref "J2") (pin "29") (pinfunction "29_29") (pintype "passive+no_connect"))
    )
    (net (code "53") (name "unconnected-(K1-PadNC)") (class "Default")
      (node (ref "K1") (pin "NC") (pinfunction "NC_NC") (pintype "passive"))
    )
    (net (code "54") (name "unconnected-(K2-PadNC)") (class "Default")
      (node (ref "K2") (pin "NC") (pinfunction "NC_NC") (pintype "passive"))
    )
    (net (code "55") (name "unconnected-(T1-Pad2)") (class "Default")
      (node (ref "T1") (pin "2") (pinfunction "2_2") (pintype "passive+no_connect"))
    )
    (net (code "56") (name "unconnected-(T1-Pad3)") (class "Default")
      (node (ref "T1") (pin "3") (pinfunction "3_3") (pintype "passive+no_connect"))
    )
    (net (code "57") (name "unconnected-(T1-Pad4)") (class "Default")
      (node (ref "T1") (pin "4") (pinfunction "4_4") (pintype "passive+no_connect"))
    )
    (net (code "58") (name "unconnected-(T1-Pad8)") (class "Default")
      (node (ref "T1") (pin "8") (pinfunction "8_8") (pintype "passive+no_connect"))
    )
    (net (code "59") (name "unconnected-(T1-Pad9)") (class "Default")
      (node (ref "T1") (pin "9") (pinfunction "9_9") (pintype "passive"))
    )
    (net (code "60") (name "unconnected-(T1-Pad10)") (class "Default")
      (node (ref "T1") (pin "10") (pinfunction "10_10") (pintype "passive"))
    )
  )
)
